# 468332_031_3_2.net
KiCad netlist of a schematic drawn in Altium Designer
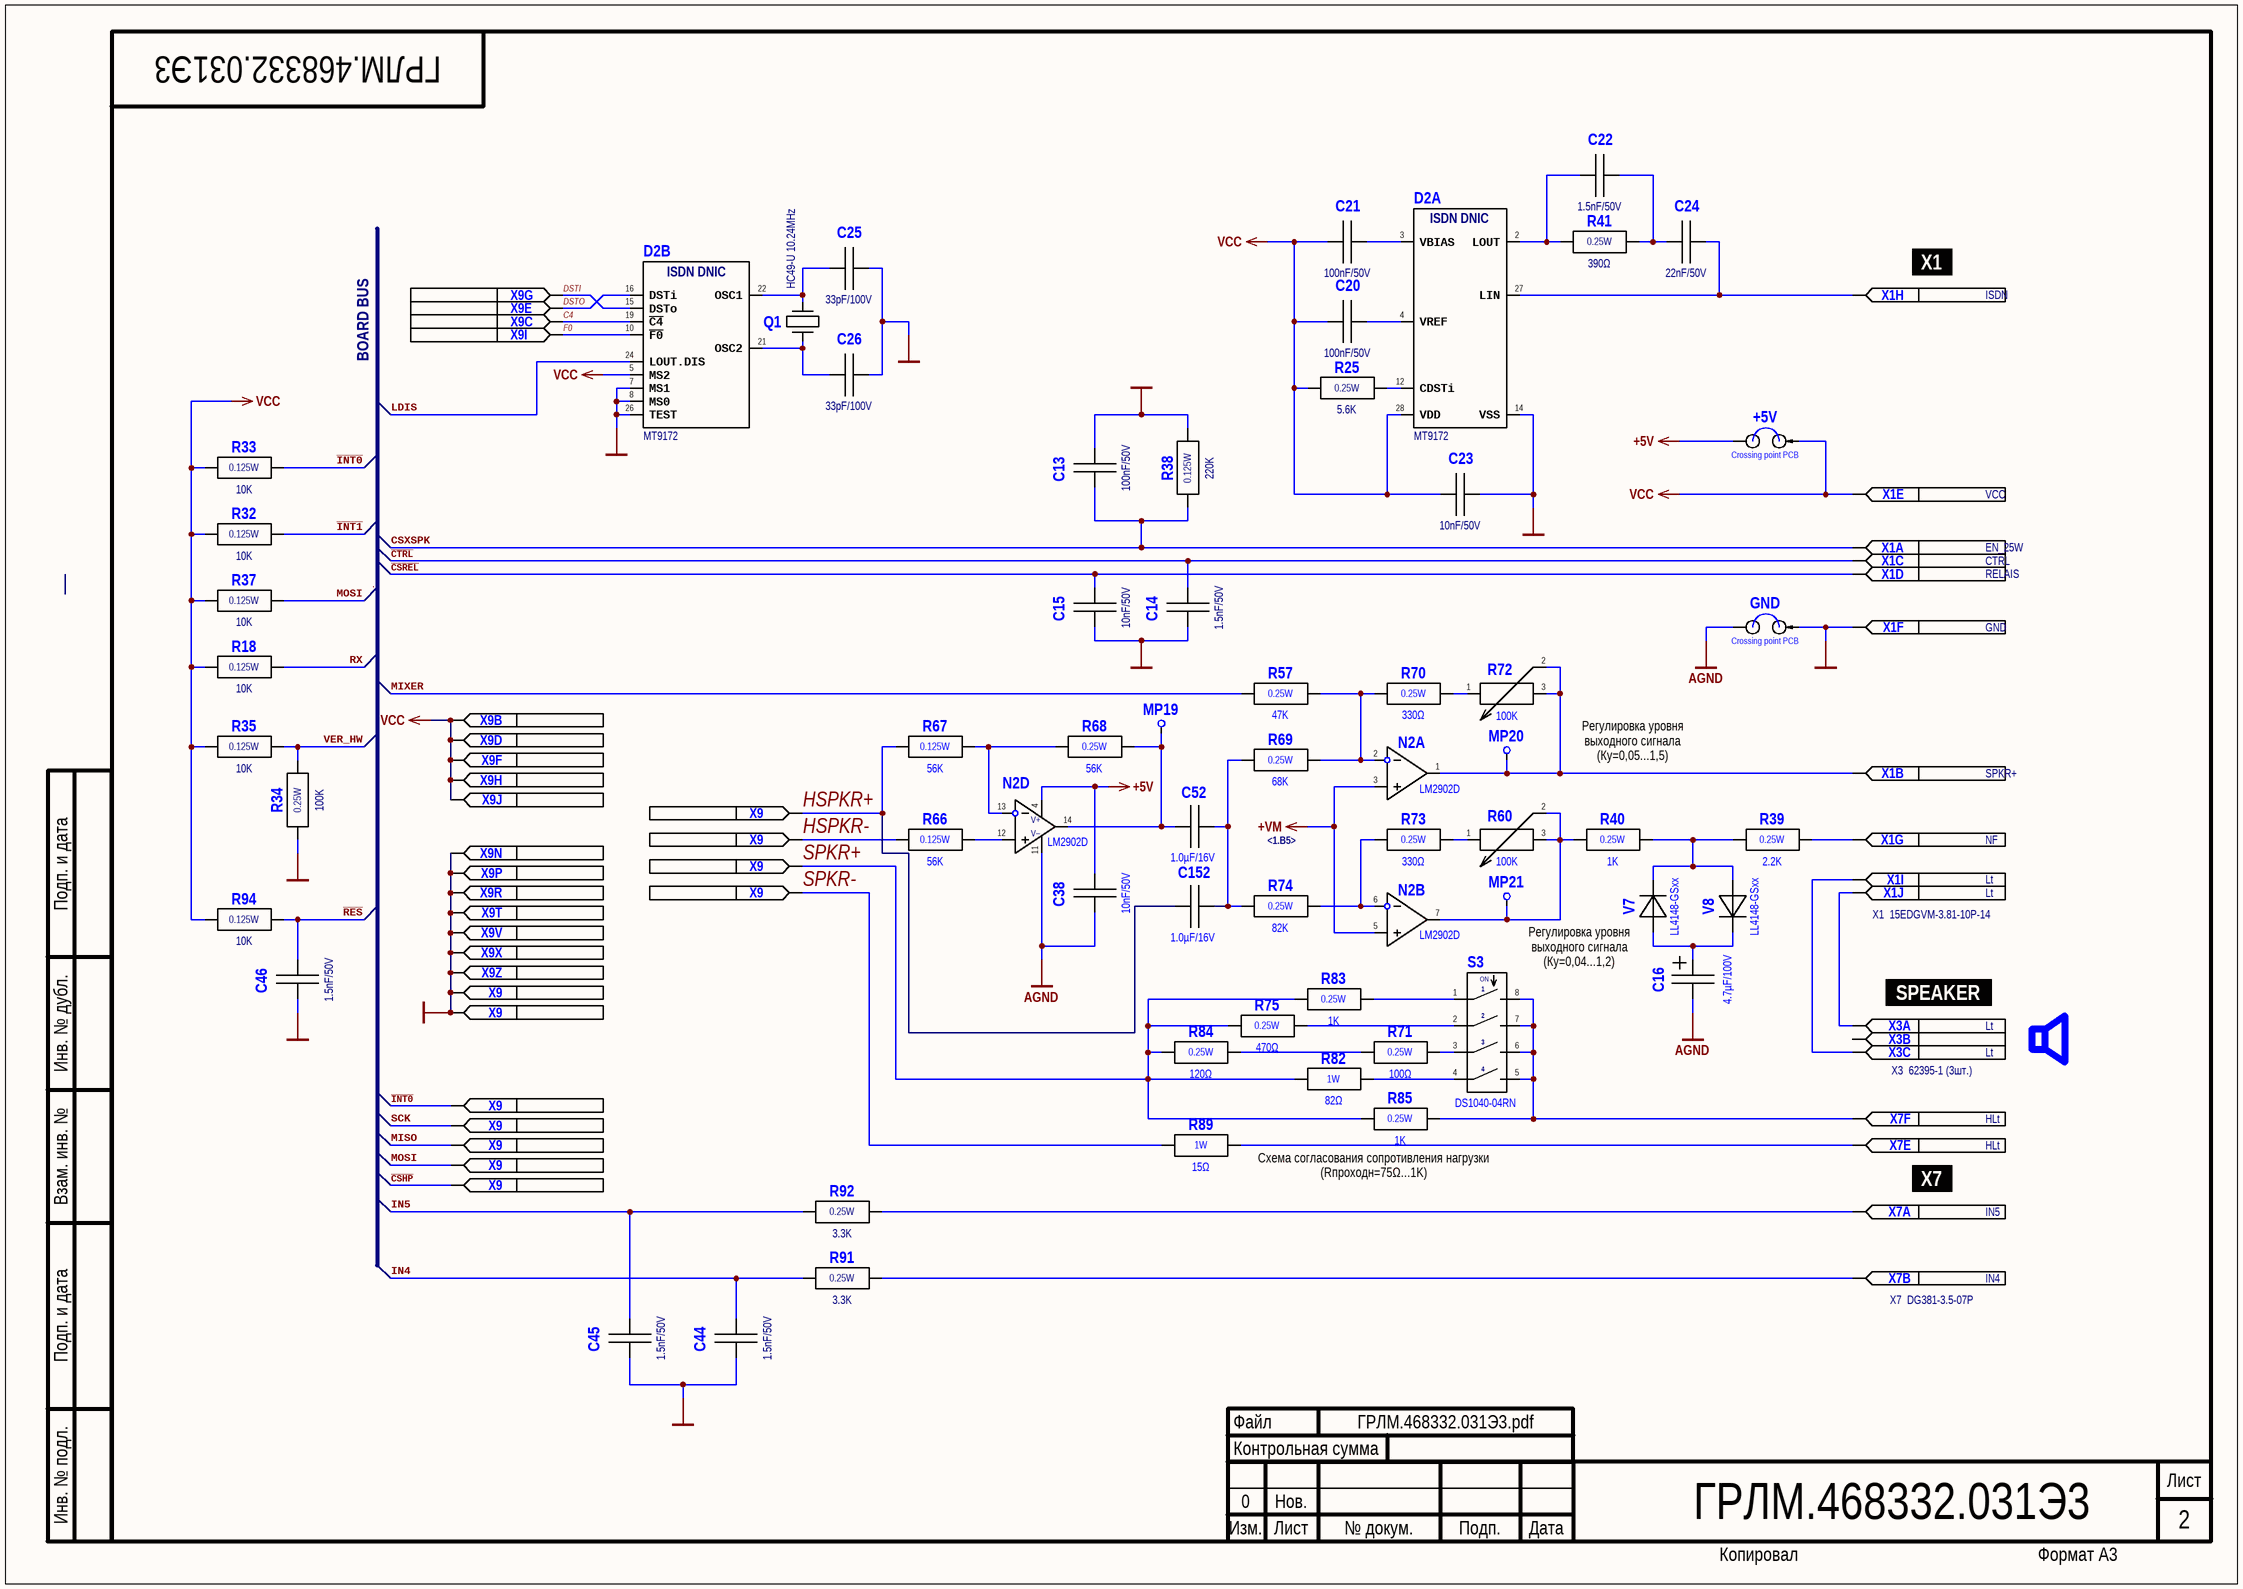
[diagram p0: ГРЛМ.468332.031Э3 (Лист 2).SchDoc]

(export (version "E")
  (design (tool "Eeschema 10.0.6"))
  (components
    (comp (ref "+5V")
      (value "Crossing point PCB")
      (footprint "Crossing point PCB")
      (description "Crossing point")
      (libsource (lib "R 6 DSX 04") (part "Crossing point PCB"))
    )
    (comp (ref "C13")
      (value "100nF/50V")
      (footprint "SMD Capacitor 0805")
      (fields (field (name "PARTNUMBER") "CC0805KRX7R9BB104"))
      (libsource (lib "R 6 DSX 04") (part "Capacitor"))
    )
    (comp (ref "C14")
      (value "1.5nF/50V")
      (footprint "SMD Capacitor 0805")
      (fields (field (name "PARTNUMBER") "CC0805JRNPO9BN152"))
      (libsource (lib "R 6 DSX 04") (part "Capacitor"))
    )
    (comp (ref "C15")
      (value "10nF/50V")
      (footprint "SMD Capacitor 0805")
      (fields (field (name "PARTNUMBER") "CC0805KRX7R9BB103"))
      (libsource (lib "R 6 DSX 04") (part "Capacitor"))
    )
    (comp (ref "C16")
      (value "4.7µF/100V")
      (footprint "Capacitor  electrolytic 5x11mm")
      (description "Capacitor Electrolytic")
      (fields (field (name "PARTNUMBER") "К50-35-100В-4,7мкФ 5х11мм"))
      (libsource (lib "R 6 DSX 04") (part "Capacitor Electrolytic"))
    )
    (comp (ref "C20")
      (value "100nF/50V")
      (footprint "SMD Capacitor 0805")
      (fields (field (name "PARTNUMBER") "CC0805KRX7R9BB104"))
      (libsource (lib "R 6 DSX 04") (part "Capacitor"))
    )
    (comp (ref "C21")
      (value "100nF/50V")
      (footprint "SMD Capacitor 0805")
      (fields (field (name "PARTNUMBER") "CC0805KRX7R9BB104"))
      (libsource (lib "R 6 DSX 04") (part "Capacitor"))
    )
    (comp (ref "C22")
      (value "1.5nF/50V")
      (footprint "SMD Capacitor 0805")
      (fields (field (name "PARTNUMBER") "CC0805JRNPO9BN152"))
      (libsource (lib "R 6 DSX 04") (part "Capacitor"))
    )
    (comp (ref "C23")
      (value "10nF/50V")
      (footprint "SMD Capacitor 0805")
      (fields (field (name "PARTNUMBER") "CC0805KRX7R9BB103"))
      (libsource (lib "R 6 DSX 04") (part "Capacitor"))
    )
    (comp (ref "C24")
      (value "22nF/50V")
      (footprint "SMD Capacitor 0805")
      (fields (field (name "PARTNUMBER") "CC0805KRX7R9BB223"))
      (libsource (lib "R 6 DSX 04") (part "Capacitor"))
    )
    (comp (ref "C25")
      (value "33pF/100V")
      (footprint "SMD Capacitor 0805")
      (fields (field (name "PARTNUMBER") "CC0805JRNPO0BN330"))
      (libsource (lib "R 6 DSX 04") (part "Capacitor"))
    )
    (comp (ref "C26")
      (value "33pF/100V")
      (footprint "SMD Capacitor 0805")
      (fields (field (name "PARTNUMBER") "CC0805JRNPO0BN330"))
      (libsource (lib "R 6 DSX 04") (part "Capacitor"))
    )
    (comp (ref "C38")
      (value "10nF/50V")
      (footprint "SMD Capacitor 0805")
      (fields (field (name "PARTNUMBER") "CC0805KRX7R9BB103"))
      (libsource (lib "R 6 DSX 04") (part "Capacitor"))
    )
    (comp (ref "C44")
      (value "1.5nF/50V")
      (footprint "SMD Capacitor 0805")
      (fields (field (name "PARTNUMBER") "CC0805JRNPO9BN152"))
      (libsource (lib "R 6 DSX 04") (part "Capacitor"))
    )
    (comp (ref "C45")
      (value "1.5nF/50V")
      (footprint "SMD Capacitor 0805")
      (fields (field (name "PARTNUMBER") "CC0805JRNPO9BN152"))
      (libsource (lib "R 6 DSX 04") (part "Capacitor"))
    )
    (comp (ref "C46")
      (value "1.5nF/50V")
      (footprint "SMD Capacitor 0805")
      (fields (field (name "PARTNUMBER") "CC0805JRNPO9BN152"))
      (libsource (lib "R 6 DSX 04") (part "Capacitor"))
    )
    (comp (ref "C52")
      (value "1.0µF/16V")
      (footprint "SMD Capacitor 0805")
      (fields (field (name "PARTNUMBER") "GRM21BR71C105K"))
      (libsource (lib "R 6 DSX 04") (part "Capacitor"))
    )
    (comp (ref "C152")
      (value "1.0µF/16V")
      (footprint "SMD Capacitor 0805")
      (fields (field (name "PARTNUMBER") "GRM21BR71C105K"))
      (libsource (lib "R 6 DSX 04") (part "Capacitor"))
    )
    (comp (ref "D2")
      (value "MT9172")
      (footprint "PLCC28 SMD")
      (libsource (lib "R 6 DSX 04") (part "MT9172 (PLCC28)"))
    )
    (comp (ref "GND")
      (value "Crossing point PCB")
      (footprint "Crossing point PCB")
      (description "Crossing point")
      (libsource (lib "R 6 DSX 04") (part "Crossing point PCB"))
    )
    (comp (ref "MP19")
      (value "TestPoint SMD")
      (footprint "Test point SMD")
      (description "SMD Test Point")
      (libsource (lib "R 1 DTS 011") (part "TestPoint SMD"))
    )
    (comp (ref "MP20")
      (value "TestPoint SMD")
      (footprint "Test point SMD")
      (description "SMD Test Point")
      (libsource (lib "R 1 DTS 011") (part "TestPoint SMD"))
    )
    (comp (ref "MP21")
      (value "TestPoint SMD")
      (footprint "Test point SMD")
      (description "SMD Test Point")
      (libsource (lib "R 1 DTS 011") (part "TestPoint SMD"))
    )
    (comp (ref "N2")
      (value "LM2902D")
      (footprint "SO14")
      (description "Low-power quad operational amplifiers\r\nSO-14")
      (fields (field (name "PARTNUMBER") "LM2902D(DT)"))
      (libsource (lib "R 6 DSX 04") (part "LM2902D(DT)"))
    )
    (comp (ref "Q1")
      (value "HC49-U 10.24MHz")
      (footprint "HC-49U Quartz Crystal Resonator")
      (description "Quartz-crystal resonator")
      (libsource (lib "R 6 DSX 04") (part "Quartz resonator"))
    )
    (comp (ref "R18")
      (value "10K")
      (footprint "SMD Resistor 0805")
      (fields (field (name "PARTNUMBER") "RC0805JR-0710KL") (field (name "POWER DISSIPATION") "0.125W"))
      (libsource (lib "R 6 DSX 04") (part "Resistor"))
    )
    (comp (ref "R25")
      (value "5.6K")
      (footprint "SMD Resistor 1206")
      (fields (field (name "PARTNUMBER") "RC1206JR-075K6L") (field (name "POWER DISSIPATION") "0.25W"))
      (libsource (lib "R 6 DSX 04") (part "Resistor"))
    )
    (comp (ref "R32")
      (value "10K")
      (footprint "SMD Resistor 0805")
      (fields (field (name "PARTNUMBER") "RC0805JR-0710KL") (field (name "POWER DISSIPATION") "0.125W"))
      (libsource (lib "R 6 DSX 04") (part "Resistor"))
    )
    (comp (ref "R33")
      (value "10K")
      (footprint "SMD Resistor 0805")
      (fields (field (name "PARTNUMBER") "RC0805JR-0710KL") (field (name "POWER DISSIPATION") "0.125W"))
      (libsource (lib "R 6 DSX 04") (part "Resistor"))
    )
    (comp (ref "R34")
      (value "100K")
      (footprint "SMD Resistor 1206")
      (fields (field (name "PARTNUMBER") "RC1206JR-07100KL") (field (name "POWER DISSIPATION") "0.25W"))
      (libsource (lib "R 6 DSX 04") (part "Resistor"))
    )
    (comp (ref "R35")
      (value "10K")
      (footprint "SMD Resistor 0805")
      (fields (field (name "PARTNUMBER") "RC0805JR-0710KL") (field (name "POWER DISSIPATION") "0.125W"))
      (libsource (lib "R 6 DSX 04") (part "Resistor"))
    )
    (comp (ref "R37")
      (value "10K")
      (footprint "SMD Resistor 0805")
      (fields (field (name "PARTNUMBER") "RC0805JR-0710KL") (field (name "POWER DISSIPATION") "0.125W"))
      (libsource (lib "R 6 DSX 04") (part "Resistor"))
    )
    (comp (ref "R38")
      (value "220K")
      (footprint "SMD Resistor 0805")
      (fields (field (name "PARTNUMBER") "RC0805JR-07220KL") (field (name "POWER DISSIPATION") "0.125W"))
      (libsource (lib "R 6 DSX 04") (part "Resistor"))
    )
    (comp (ref "R39")
      (value "2.2K")
      (footprint "SMD Resistor 1206")
      (fields (field (name "PARTNUMBER") "RC1206JR-072K2L") (field (name "POWER DISSIPATION") "0.25W"))
      (libsource (lib "R 6 DSX 04") (part "Resistor"))
    )
    (comp (ref "R40")
      (value "1K")
      (footprint "SMD Resistor 1206")
      (fields (field (name "PARTNUMBER") "RC1206JR-071KL") (field (name "POWER DISSIPATION") "0.25W"))
      (libsource (lib "R 6 DSX 04") (part "Resistor"))
    )
    (comp (ref "R41")
      (value "390Ω")
      (footprint "SMD Resistor 1206")
      (fields (field (name "PARTNUMBER") "RC1206JR-07390RL") (field (name "POWER DISSIPATION") "0.25W"))
      (libsource (lib "R 6 DSX 04") (part "Resistor"))
    )
    (comp (ref "R57")
      (value "47K")
      (footprint "SMD Resistor 1206")
      (fields (field (name "PARTNUMBER") "RC1206JR-0747KL") (field (name "POWER DISSIPATION") "0.25W"))
      (libsource (lib "R 6 DSX 04") (part "Resistor"))
    )
    (comp (ref "R60")
      (value "100K")
      (footprint "3362H Square Trimming Potentiometer")
      (fields (field (name "PARTNUMBER") "3362H-1-104LF"))
      (libsource (lib "R 6 DSX 04") (part "Resistor adjustable"))
    )
    (comp (ref "R66")
      (value "56K")
      (footprint "SMD Resistor 0805")
      (fields (field (name "PARTNUMBER") "RC0805JR-0756KL") (field (name "POWER DISSIPATION") "0.125W"))
      (libsource (lib "R 6 DSX 04") (part "Resistor"))
    )
    (comp (ref "R67")
      (value "56K")
      (footprint "SMD Resistor 0805")
      (fields (field (name "PARTNUMBER") "RC0805JR-0756KL") (field (name "POWER DISSIPATION") "0.125W"))
      (libsource (lib "R 6 DSX 04") (part "Resistor"))
    )
    (comp (ref "R68")
      (value "56K")
      (footprint "SMD Resistor 1206")
      (fields (field (name "PARTNUMBER") "RC1206JR-0756KL") (field (name "POWER DISSIPATION") "0.25W"))
      (libsource (lib "R 6 DSX 04") (part "Resistor"))
    )
    (comp (ref "R69")
      (value "68K")
      (footprint "SMD Resistor 1206")
      (fields (field (name "PARTNUMBER") "RC1206JR-0768KL") (field (name "POWER DISSIPATION") "0.25W"))
      (libsource (lib "R 6 DSX 04") (part "Resistor"))
    )
    (comp (ref "R70")
      (value "330Ω")
      (footprint "SMD Resistor 1206")
      (fields (field (name "PARTNUMBER") "RC1206JR-07330RL") (field (name "POWER DISSIPATION") "0.25W"))
      (libsource (lib "R 6 DSX 04") (part "Resistor"))
    )
    (comp (ref "R71")
      (value "100Ω")
      (footprint "SMD Resistor 1206")
      (fields (field (name "PARTNUMBER") "RC1206JR-07100RL") (field (name "POWER DISSIPATION") "0.25W"))
      (libsource (lib "R 6 DSX 04") (part "Resistor"))
    )
    (comp (ref "R72")
      (value "100K")
      (footprint "3362H Square Trimming Potentiometer")
      (fields (field (name "PARTNUMBER") "3362H-1-104LF"))
      (libsource (lib "R 6 DSX 04") (part "Resistor adjustable"))
    )
    (comp (ref "R73")
      (value "330Ω")
      (footprint "SMD Resistor 1206")
      (fields (field (name "PARTNUMBER") "RC1206JR-07330RL") (field (name "POWER DISSIPATION") "0.25W"))
      (libsource (lib "R 6 DSX 04") (part "Resistor"))
    )
    (comp (ref "R74")
      (value "82K")
      (footprint "SMD Resistor 1206")
      (fields (field (name "PARTNUMBER") "RC1206JR-0782KL") (field (name "POWER DISSIPATION") "0.25W"))
      (libsource (lib "R 6 DSX 04") (part "Resistor"))
    )
    (comp (ref "R75")
      (value "470Ω")
      (footprint "SMD Resistor 1206")
      (fields (field (name "PARTNUMBER") "RC1206JR-07470RL") (field (name "POWER DISSIPATION") "0.25W"))
      (libsource (lib "R 6 DSX 04") (part "Resistor"))
    )
    (comp (ref "R82")
      (value "82Ω")
      (footprint "Resistor FMP100 1W Yageo")
      (fields (field (name "PARTNUMBER") "FMP100JT-52-82R") (field (name "POWER DISSIPATION") "1W"))
      (libsource (lib "R 6 DSX 04") (part "Resistor"))
    )
    (comp (ref "R83")
      (value "1K")
      (footprint "SMD Resistor 1206")
      (fields (field (name "PARTNUMBER") "RC1206JR-071KL") (field (name "POWER DISSIPATION") "0.25W"))
      (libsource (lib "R 6 DSX 04") (part "Resistor"))
    )
    (comp (ref "R84")
      (value "120Ω")
      (footprint "SMD Resistor 1206")
      (fields (field (name "PARTNUMBER") "RC1206JR-07120RL") (field (name "POWER DISSIPATION") "0.25W"))
      (libsource (lib "R 6 DSX 04") (part "Resistor"))
    )
    (comp (ref "R85")
      (value "1K")
      (footprint "SMD Resistor 1206")
      (fields (field (name "PARTNUMBER") "RC1206JR-071KL") (field (name "POWER DISSIPATION") "0.25W"))
      (libsource (lib "R 6 DSX 04") (part "Resistor"))
    )
    (comp (ref "R89")
      (value "15Ω")
      (footprint "Resistor FMP100 1W Yageo")
      (fields (field (name "PARTNUMBER") "FMP100JT-52-15R") (field (name "POWER DISSIPATION") "1W"))
      (libsource (lib "R 6 DSX 04") (part "Resistor"))
    )
    (comp (ref "R91")
      (value "3.3K")
      (footprint "SMD Resistor 1206")
      (fields (field (name "PARTNUMBER") "RC1206JR-073K3L") (field (name "POWER DISSIPATION") "0.25W"))
      (libsource (lib "R 6 DSX 04") (part "Resistor"))
    )
    (comp (ref "R92")
      (value "3.3K")
      (footprint "SMD Resistor 1206")
      (fields (field (name "PARTNUMBER") "RC1206JR-073K3L") (field (name "POWER DISSIPATION") "0.25W"))
      (libsource (lib "R 6 DSX 04") (part "Resistor"))
    )
    (comp (ref "R94")
      (value "10K")
      (footprint "SMD Resistor 0805")
      (fields (field (name "PARTNUMBER") "RC0805JR-0710KL") (field (name "POWER DISSIPATION") "0.125W"))
      (libsource (lib "R 6 DSX 04") (part "Resistor"))
    )
    (comp (ref "S3")
      (value "DS1040-04RN")
      (footprint "DS1040-04 DIP Switch")
      (description "DIP-switch, 4 NO Groups, by Connfly")
      (libsource (lib "R 6 DSX 04") (part "DIP-SWITCH DS1040-04RN"))
    )
    (comp (ref "V7")
      (value "LL4148-GSxx")
      (footprint "Diode SOD80C (Anode pin 1)")
      (description "Diode")
      (libsource (lib "R 6 DSX 04") (part "Diode"))
    )
    (comp (ref "V8")
      (value "LL4148-GSxx")
      (footprint "Diode SOD80C (Anode pin 1)")
      (description "Diode")
      (libsource (lib "R 6 DSX 04") (part "Diode"))
    )
    (comp (ref "X1")
      (value "Connector 10 pins (universal)")
      (footprint "Connector 15EDGVM-3.81-10P")
      (fields (field (name "PARTNUMBER") "15EDGVM-3.81-10P-14"))
      (libsource (lib "R 6 DSX 04") (part "Connector 10 pins (universal)"))
    )
    (comp (ref "X3")
      (value "62395-1 (3ps)")
      (footprint "Faston Connector 3 x 2.8 mm")
      (fields (field (name "PARTNUMBER") "62395-1 (3 ps)"))
      (libsource (lib "R 6 DSX 04") (part "Connector 3 pins (universal)"))
    )
    (comp (ref "X7")
      (value "DG381-3.5-07P")
      (footprint "DG381-3.5-07P Terminals")
      (libsource (lib "R 6 DSX 04") (part "Connector 7 pins (universal)"))
    )
    (comp (ref "X9")
      (value "5177983-2")
      (footprint "Connector 5177983-2")
      (libsource (lib "R 6 DSX 04") (part "Connector 60 pins (universal)"))
    )
  )
  (nets
    (net (code "2") (name "+5V") (class "Default")
      (node (ref "+5V") (pin "2") (pinfunction "2_2") (pintype "passive"))
      (node (ref "C38") (pin "2") (pinfunction "2_2") (pintype "passive"))
      (node (ref "N2") (pin "4") (pintype "passive"))
    )
    (net (code "3") (name "+VM") (class "Default")
      (node (ref "N2") (pin "3") (pintype "passive"))
      (node (ref "N2") (pin "5") (pintype "passive"))
    )
    (net (code "4") (name "/C4") (class "Default")
      (node (ref "D2") (pin "19") (pinfunction "~{C4}_19") (pintype "passive"))
      (node (ref "X9") (pin "3") (pinfunction "3_3") (pintype "passive"))
    )
    (net (code "5") (name "/CSXSPK") (class "Default")
      (node (ref "C13") (pin "1") (pinfunction "1_1") (pintype "passive"))
      (node (ref "R38") (pin "1") (pinfunction "1_1") (pintype "passive"))
      (node (ref "X1") (pin "1") (pinfunction "1_1") (pintype "passive"))
    )
    (net (code "6") (name "/DSTI") (class "Default")
      (node (ref "D2") (pin "15") (pinfunction "DSTo_15") (pintype "passive"))
      (node (ref "X9") (pin "7") (pinfunction "7_7") (pintype "passive"))
    )
    (net (code "7") (name "/DSTO") (class "Default")
      (node (ref "D2") (pin "16") (pinfunction "DSTi_16") (pintype "passive"))
      (node (ref "X9") (pin "5") (pinfunction "5_5") (pintype "passive"))
    )
    (net (code "8") (name "/F0") (class "Default")
      (node (ref "D2") (pin "10") (pinfunction "~{F0}_10") (pintype "passive"))
      (node (ref "X9") (pin "9") (pinfunction "9_9") (pintype "passive"))
    )
    (net (code "9") (name "/HSPKR+") (class "Default")
      (node (ref "C152") (pin "2") (pinfunction "2_2") (pintype "passive"))
      (node (ref "R67") (pin "1") (pinfunction "1_1") (pintype "passive"))
      (node (ref "X9") (pin "33") (pinfunction "33_33") (pintype "passive"))
    )
    (net (code "10") (name "/HSPKR-") (class "Default")
      (node (ref "R66") (pin "1") (pinfunction "1_1") (pintype "passive"))
      (node (ref "X9") (pin "31") (pinfunction "31_31") (pintype "passive"))
    )
    (net (code "11") (name "/IN4") (class "Default")
      (node (ref "C44") (pin "2") (pinfunction "2_2") (pintype "passive"))
      (node (ref "R91") (pin "1") (pinfunction "1_1") (pintype "passive"))
    )
    (net (code "12") (name "/IN5") (class "Default")
      (node (ref "C45") (pin "2") (pinfunction "2_2") (pintype "passive"))
      (node (ref "R92") (pin "1") (pinfunction "1_1") (pintype "passive"))
    )
    (net (code "13") (name "/LDIS") (class "Default")
      (node (ref "D2") (pin "24") (pinfunction "LOUT.DIS_24") (pintype "passive"))
    )
    (net (code "14") (name "/MISO") (class "Default")
      (node (ref "X9") (pin "60") (pinfunction "60_60") (pintype "passive"))
    )
    (net (code "15") (name "/MIXER") (class "Default")
      (node (ref "R57") (pin "1") (pinfunction "1_1") (pintype "passive"))
    )
    (net (code "16") (name "/MOSI") (class "Default")
      (node (ref "R37") (pin "2") (pinfunction "2_2") (pintype "passive"))
      (node (ref "X9") (pin "58") (pinfunction "58_58") (pintype "passive"))
    )
    (net (code "17") (name "/RX") (class "Default")
      (node (ref "R18") (pin "2") (pinfunction "2_2") (pintype "passive"))
    )
    (net (code "18") (name "/SCK") (class "Default")
      (node (ref "X9") (pin "57") (pinfunction "57_57") (pintype "passive"))
    )
    (net (code "19") (name "/SPKR+") (class "Default")
      (node (ref "R75") (pin "1") (pinfunction "1_1") (pintype "passive"))
      (node (ref "R82") (pin "1") (pinfunction "1_1") (pintype "passive"))
      (node (ref "R83") (pin "1") (pinfunction "1_1") (pintype "passive"))
      (node (ref "R84") (pin "1") (pinfunction "1_1") (pintype "passive"))
      (node (ref "R85") (pin "1") (pinfunction "1_1") (pintype "passive"))
      (node (ref "X9") (pin "37") (pinfunction "37_37") (pintype "passive"))
    )
    (net (code "20") (name "/SPKR-") (class "Default")
      (node (ref "R89") (pin "1") (pinfunction "1_1") (pintype "passive"))
      (node (ref "X9") (pin "35") (pinfunction "35_35") (pintype "passive"))
    )
    (net (code "21") (name "/VER_HW") (class "Default")
      (node (ref "R34") (pin "2") (pinfunction "2_2") (pintype "passive"))
      (node (ref "R35") (pin "2") (pinfunction "2_2") (pintype "passive"))
    )
    (net (code "23") (name "/~{CSHP}") (class "Default")
      (node (ref "X9") (pin "56") (pinfunction "56_56") (pintype "passive"))
    )
    (net (code "24") (name "/~{CSREL}") (class "Default")
      (node (ref "C15") (pin "2") (pinfunction "2_2") (pintype "passive"))
      (node (ref "X1") (pin "4") (pinfunction "4_4") (pintype "passive"))
    )
    (net (code "25") (name "/~{CTRL}") (class "Default")
      (node (ref "C14") (pin "2") (pinfunction "2_2") (pintype "passive"))
      (node (ref "X1") (pin "3") (pinfunction "3_3") (pintype "passive"))
    )
    (net (code "26") (name "/~{INT0}") (class "Default")
      (node (ref "R33") (pin "2") (pinfunction "2_2") (pintype "passive"))
      (node (ref "X9") (pin "59") (pinfunction "59_59") (pintype "passive"))
    )
    (net (code "27") (name "/~{INT1}") (class "Default")
      (node (ref "R32") (pin "2") (pinfunction "2_2") (pintype "passive"))
    )
    (net (code "28") (name "/~{RES}") (class "Default")
      (node (ref "C46") (pin "2") (pinfunction "2_2") (pintype "passive"))
      (node (ref "R94") (pin "2") (pinfunction "2_2") (pintype "passive"))
    )
    (net (code "29") (name "AGND") (class "Default")
      (node (ref "C16") (pin "2") (pinfunction "2_2") (pintype "passive"))
      (node (ref "C38") (pin "1") (pinfunction "1_1") (pintype "passive"))
      (node (ref "GND") (pin "2") (pinfunction "2_2") (pintype "passive"))
      (node (ref "N2") (pin "11") (pintype "passive"))
    )
    (net (code "30") (name "DGND") (class "Default")
      (node (ref "C13") (pin "2") (pinfunction "2_2") (pintype "passive"))
      (node (ref "C14") (pin "1") (pinfunction "1_1") (pintype "passive"))
      (node (ref "C15") (pin "1") (pinfunction "1_1") (pintype "passive"))
      (node (ref "C23") (pin "1") (pinfunction "1_1") (pintype "passive"))
      (node (ref "C25") (pin "1") (pinfunction "1_1") (pintype "passive"))
      (node (ref "C26") (pin "1") (pinfunction "1_1") (pintype "passive"))
      (node (ref "C44") (pin "1") (pinfunction "1_1") (pintype "passive"))
      (node (ref "C45") (pin "1") (pinfunction "1_1") (pintype "passive"))
      (node (ref "C46") (pin "1") (pinfunction "1_1") (pintype "passive"))
      (node (ref "D2") (pin "14") (pinfunction "VSS_14") (pintype "passive"))
      (node (ref "D2") (pin "26") (pinfunction "TEST_26") (pintype "passive"))
      (node (ref "D2") (pin "7") (pinfunction "MS1_7") (pintype "passive"))
      (node (ref "D2") (pin "8") (pinfunction "MS0_8") (pintype "passive"))
      (node (ref "GND") (pin "1") (pinfunction "1_1") (pintype "passive"))
      (node (ref "R34") (pin "1") (pinfunction "1_1") (pintype "passive"))
      (node (ref "R38") (pin "2") (pinfunction "2_2") (pintype "passive"))
      (node (ref "X1") (pin "6") (pinfunction "6_6") (pintype "passive"))
      (node (ref "X9") (pin "14") (pinfunction "14_14") (pintype "passive"))
      (node (ref "X9") (pin "16") (pinfunction "16_16") (pintype "passive"))
      (node (ref "X9") (pin "18") (pinfunction "18_18") (pintype "passive"))
      (node (ref "X9") (pin "20") (pinfunction "20_20") (pintype "passive"))
      (node (ref "X9") (pin "22") (pinfunction "22_22") (pintype "passive"))
      (node (ref "X9") (pin "24") (pinfunction "24_24") (pintype "passive"))
      (node (ref "X9") (pin "26") (pinfunction "26_26") (pintype "passive"))
      (node (ref "X9") (pin "28") (pinfunction "28_28") (pintype "passive"))
      (node (ref "X9") (pin "30") (pinfunction "30_30") (pintype "passive"))
    )
    (net (code "31") (name "Net-(C16-Pad1)") (class "Default")
      (node (ref "C16") (pin "1") (pinfunction "1_1") (pintype "passive"))
      (node (ref "V7") (pin "1") (pinfunction "1_1") (pintype "passive"))
      (node (ref "V8") (pin "2") (pinfunction "2_2") (pintype "passive"))
    )
    (net (code "32") (name "Net-(C22-Pad1)") (class "Default")
      (node (ref "C22") (pin "1") (pinfunction "1_1") (pintype "passive"))
      (node (ref "C24") (pin "2") (pinfunction "2_2") (pintype "passive"))
      (node (ref "R41") (pin "1") (pinfunction "1_1") (pintype "passive"))
    )
    (net (code "33") (name "Net-(C52-Pad2)") (class "Default")
      (node (ref "C52") (pin "2") (pinfunction "2_2") (pintype "passive"))
      (node (ref "MP19") (pin "1") (pinfunction "1_1") (pintype "passive"))
      (node (ref "N2") (pin "14") (pintype "passive"))
      (node (ref "R68") (pin "2") (pinfunction "2_2") (pintype "passive"))
    )
    (net (code "34") (name "Net-(C152-Pad1)") (class "Default")
      (node (ref "C152") (pin "1") (pinfunction "1_1") (pintype "passive"))
      (node (ref "C52") (pin "1") (pinfunction "1_1") (pintype "passive"))
      (node (ref "R69") (pin "1") (pinfunction "1_1") (pintype "passive"))
      (node (ref "R74") (pin "1") (pinfunction "1_1") (pintype "passive"))
    )
    (net (code "35") (name "Net-(D2A-CDSTi)") (class "Default")
      (node (ref "D2") (pin "12") (pinfunction "CDSTi_12") (pintype "passive"))
      (node (ref "R25") (pin "1") (pinfunction "1_1") (pintype "passive"))
    )
    (net (code "36") (name "Net-(D2A-LIN)") (class "Default")
      (node (ref "C24") (pin "1") (pinfunction "1_1") (pintype "passive"))
      (node (ref "D2") (pin "27") (pinfunction "LIN_27") (pintype "passive"))
      (node (ref "X1") (pin "8") (pinfunction "8_8") (pintype "passive"))
    )
    (net (code "37") (name "Net-(D2A-LOUT)") (class "Default")
      (node (ref "C22") (pin "2") (pinfunction "2_2") (pintype "passive"))
      (node (ref "D2") (pin "2") (pinfunction "LOUT_2") (pintype "passive"))
      (node (ref "R41") (pin "2") (pinfunction "2_2") (pintype "passive"))
    )
    (net (code "38") (name "Net-(D2A-VBIAS)") (class "Default")
      (node (ref "C21") (pin "1") (pinfunction "1_1") (pintype "passive"))
      (node (ref "D2") (pin "3") (pinfunction "VBIAS_3") (pintype "passive"))
    )
    (net (code "39") (name "Net-(D2A-VREF)") (class "Default")
      (node (ref "C20") (pin "1") (pinfunction "1_1") (pintype "passive"))
      (node (ref "D2") (pin "4") (pinfunction "VREF_4") (pintype "passive"))
    )
    (net (code "40") (name "Net-(D2B-OSC1)") (class "Default")
      (node (ref "C25") (pin "2") (pinfunction "2_2") (pintype "passive"))
      (node (ref "D2") (pin "22") (pinfunction "OSC1_22") (pintype "passive"))
      (node (ref "Q1") (pin "2") (pinfunction "2_2") (pintype "passive"))
    )
    (net (code "41") (name "Net-(D2B-OSC2)") (class "Default")
      (node (ref "C26") (pin "2") (pinfunction "2_2") (pintype "passive"))
      (node (ref "D2") (pin "21") (pinfunction "OSC2_21") (pintype "passive"))
      (node (ref "Q1") (pin "1") (pinfunction "1_1") (pintype "passive"))
    )
    (net (code "42") (name "Net-(MP20-Pad1)") (class "Default")
      (node (ref "MP20") (pin "1") (pinfunction "1_1") (pintype "passive"))
      (node (ref "N2") (pin "1") (pintype "passive"))
      (node (ref "R72") (pin "2") (pinfunction "2_2") (pintype "passive"))
      (node (ref "R72") (pin "3") (pinfunction "3_3") (pintype "passive"))
      (node (ref "X1") (pin "2") (pinfunction "2_2") (pintype "passive"))
    )
    (net (code "43") (name "Net-(MP21-Pad1)") (class "Default")
      (node (ref "MP21") (pin "1") (pinfunction "1_1") (pintype "passive"))
      (node (ref "N2") (pin "7") (pintype "passive"))
      (node (ref "R40") (pin "1") (pinfunction "1_1") (pintype "passive"))
      (node (ref "R60") (pin "2") (pinfunction "2_2") (pintype "passive"))
      (node (ref "R60") (pin "3") (pinfunction "3_3") (pintype "passive"))
    )
    (net (code "44") (name "Net-(N2-Pad2)") (class "Default")
      (node (ref "N2") (pin "2") (pintype "passive"))
      (node (ref "R57") (pin "2") (pinfunction "2_2") (pintype "passive"))
      (node (ref "R69") (pin "2") (pinfunction "2_2") (pintype "passive"))
      (node (ref "R70") (pin "1") (pinfunction "1_1") (pintype "passive"))
    )
    (net (code "45") (name "Net-(N2-Pad6)") (class "Default")
      (node (ref "N2") (pin "6") (pintype "passive"))
      (node (ref "R73") (pin "1") (pinfunction "1_1") (pintype "passive"))
      (node (ref "R74") (pin "2") (pinfunction "2_2") (pintype "passive"))
    )
    (net (code "46") (name "Net-(N2-Pad12)") (class "Default")
      (node (ref "N2") (pin "12") (pintype "passive"))
      (node (ref "R66") (pin "2") (pinfunction "2_2") (pintype "passive"))
    )
    (net (code "47") (name "Net-(N2-Pad13)") (class "Default")
      (node (ref "N2") (pin "13") (pintype "passive"))
      (node (ref "R67") (pin "2") (pinfunction "2_2") (pintype "passive"))
      (node (ref "R68") (pin "1") (pinfunction "1_1") (pintype "passive"))
    )
    (net (code "48") (name "Net-(R39-Pad1)") (class "Default")
      (node (ref "R39") (pin "1") (pinfunction "1_1") (pintype "passive"))
      (node (ref "R40") (pin "2") (pinfunction "2_2") (pintype "passive"))
      (node (ref "V7") (pin "2") (pinfunction "2_2") (pintype "passive"))
      (node (ref "V8") (pin "1") (pinfunction "1_1") (pintype "passive"))
    )
    (net (code "49") (name "Net-(R39-Pad2)") (class "Default")
      (node (ref "R39") (pin "2") (pinfunction "2_2") (pintype "passive"))
      (node (ref "X1") (pin "7") (pinfunction "7_7") (pintype "passive"))
    )
    (net (code "50") (name "Net-(R60-Pad1)") (class "Default")
      (node (ref "R60") (pin "1") (pinfunction "1_1") (pintype "passive"))
      (node (ref "R73") (pin "2") (pinfunction "2_2") (pintype "passive"))
    )
    (net (code "51") (name "Net-(R70-Pad2)") (class "Default")
      (node (ref "R70") (pin "2") (pinfunction "2_2") (pintype "passive"))
      (node (ref "R72") (pin "1") (pinfunction "1_1") (pintype "passive"))
    )
    (net (code "52") (name "Net-(R71-Pad1)") (class "Default")
      (node (ref "R71") (pin "1") (pinfunction "1_1") (pintype "passive"))
      (node (ref "R84") (pin "2") (pinfunction "2_2") (pintype "passive"))
    )
    (net (code "53") (name "Net-(R71-Pad2)") (class "Default")
      (node (ref "R71") (pin "2") (pinfunction "2_2") (pintype "passive"))
      (node (ref "S3") (pin "3") (pinfunction "3_3") (pintype "passive"))
    )
    (net (code "54") (name "Net-(R75-Pad2)") (class "Default")
      (node (ref "R75") (pin "2") (pinfunction "2_2") (pintype "passive"))
      (node (ref "S3") (pin "2") (pinfunction "2_2") (pintype "passive"))
    )
    (net (code "55") (name "Net-(R82-Pad2)") (class "Default")
      (node (ref "R82") (pin "2") (pinfunction "2_2") (pintype "passive"))
      (node (ref "S3") (pin "4") (pinfunction "4_4") (pintype "passive"))
    )
    (net (code "56") (name "Net-(R83-Pad2)") (class "Default")
      (node (ref "R83") (pin "2") (pinfunction "2_2") (pintype "passive"))
      (node (ref "S3") (pin "1") (pinfunction "1_1") (pintype "passive"))
    )
    (net (code "57") (name "Net-(R85-Pad2)") (class "Default")
      (node (ref "R85") (pin "2") (pinfunction "2_2") (pintype "passive"))
      (node (ref "S3") (pin "5") (pinfunction "5_5") (pintype "passive"))
      (node (ref "S3") (pin "6") (pinfunction "6_6") (pintype "passive"))
      (node (ref "S3") (pin "7") (pinfunction "7_7") (pintype "passive"))
      (node (ref "S3") (pin "8") (pinfunction "8_8") (pintype "passive"))
      (node (ref "X7") (pin "6") (pinfunction "6_6") (pintype "passive"))
    )
    (net (code "58") (name "Net-(R89-Pad2)") (class "Default")
      (node (ref "R89") (pin "2") (pinfunction "2_2") (pintype "passive"))
      (node (ref "X7") (pin "5") (pinfunction "5_5") (pintype "passive"))
    )
    (net (code "59") (name "Net-(R91-Pad2)") (class "Default")
      (node (ref "R91") (pin "2") (pinfunction "2_2") (pintype "passive"))
      (node (ref "X7") (pin "2") (pinfunction "2_2") (pintype "passive"))
    )
    (net (code "60") (name "Net-(R92-Pad2)") (class "Default")
      (node (ref "R92") (pin "2") (pinfunction "2_2") (pintype "passive"))
      (node (ref "X7") (pin "1") (pinfunction "1_1") (pintype "passive"))
    )
    (net (code "61") (name "Net-(X1-Pad9)") (class "Default")
      (node (ref "X1") (pin "9") (pinfunction "9_9") (pintype "passive"))
      (node (ref "X3") (pin "3") (pinfunction "3_3") (pintype "passive"))
    )
    (net (code "62") (name "Net-(X1-Pad10)") (class "Default")
      (node (ref "X1") (pin "10") (pinfunction "10_10") (pintype "passive"))
      (node (ref "X3") (pin "1") (pinfunction "1_1") (pintype "passive"))
    )
    (net (code "63") (name "VCC") (class "Default")
      (node (ref "+5V") (pin "1") (pinfunction "1_1") (pintype "passive"))
      (node (ref "C20") (pin "2") (pinfunction "2_2") (pintype "passive"))
      (node (ref "C21") (pin "2") (pinfunction "2_2") (pintype "passive"))
      (node (ref "C23") (pin "2") (pinfunction "2_2") (pintype "passive"))
      (node (ref "D2") (pin "28") (pinfunction "VDD_28") (pintype "passive"))
      (node (ref "D2") (pin "5") (pinfunction "MS2_5") (pintype "passive"))
      (node (ref "R18") (pin "1") (pinfunction "1_1") (pintype "passive"))
      (node (ref "R25") (pin "2") (pinfunction "2_2") (pintype "passive"))
      (node (ref "R32") (pin "1") (pinfunction "1_1") (pintype "passive"))
      (node (ref "R33") (pin "1") (pinfunction "1_1") (pintype "passive"))
      (node (ref "R35") (pin "1") (pinfunction "1_1") (pintype "passive"))
      (node (ref "R37") (pin "1") (pinfunction "1_1") (pintype "passive"))
      (node (ref "R94") (pin "1") (pinfunction "1_1") (pintype "passive"))
      (node (ref "X1") (pin "5") (pinfunction "5_5") (pintype "passive"))
      (node (ref "X9") (pin "10") (pinfunction "10_10") (pintype "passive"))
      (node (ref "X9") (pin "2") (pinfunction "2_2") (pintype "passive"))
      (node (ref "X9") (pin "4") (pinfunction "4_4") (pintype "passive"))
      (node (ref "X9") (pin "6") (pinfunction "6_6") (pintype "passive"))
      (node (ref "X9") (pin "8") (pinfunction "8_8") (pintype "passive"))
    )
    (net (code "64") (name "unconnected-(X3-Pad2)") (class "Default")
      (node (ref "X3") (pin "2") (pinfunction "2_2") (pintype "passive"))
    )
  )
)
